# Esquematico.net
KiCad netlist of a schematic drawn in Altium Designer
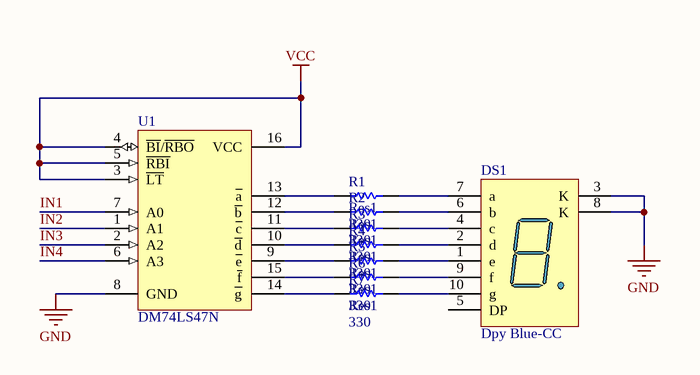
[diagram p0: Esquematico.SchDoc]

(export (version "E")
  (design (tool "Eeschema 10.0.6"))
  (components
    (comp (ref "DS1")
      (value "Dpy Blue-CC")
      (footprint "H")
      (description "14.2 mm General Purpose Blue 7-Segment Display: CC, RH DP, Gray Surface")
      (fields (field (name "PUBLISHER") "Altium Limited"))
      (libsource (lib "Miscellaneous Devices") (part "Dpy Blue-CC"))
    )
    (comp (ref "R1")
      (value "Res1")
      (footprint "AXIAL-0.3")
      (description "Resistor")
      (fields (field (name "ALTIUM_VALUE") "330") (field (name "PUBLISHER") "Altium Limited"))
      (libsource (lib "Miscellaneous Devices") (part "Res1"))
    )
    (comp (ref "R2")
      (value "Res1")
      (footprint "AXIAL-0.3")
      (description "Resistor")
      (fields (field (name "ALTIUM_VALUE") "330") (field (name "PUBLISHER") "Altium Limited"))
      (libsource (lib "Miscellaneous Devices") (part "Res1"))
    )
    (comp (ref "R3")
      (value "Res1")
      (footprint "AXIAL-0.3")
      (description "Resistor")
      (fields (field (name "ALTIUM_VALUE") "330") (field (name "PUBLISHER") "Altium Limited"))
      (libsource (lib "Miscellaneous Devices") (part "Res1"))
    )
    (comp (ref "R4")
      (value "Res1")
      (footprint "AXIAL-0.3")
      (description "Resistor")
      (fields (field (name "ALTIUM_VALUE") "330") (field (name "PUBLISHER") "Altium Limited"))
      (libsource (lib "Miscellaneous Devices") (part "Res1"))
    )
    (comp (ref "R5")
      (value "Res1")
      (footprint "AXIAL-0.3")
      (description "Resistor")
      (fields (field (name "ALTIUM_VALUE") "330") (field (name "PUBLISHER") "Altium Limited"))
      (libsource (lib "Miscellaneous Devices") (part "Res1"))
    )
    (comp (ref "R6")
      (value "Res1")
      (footprint "AXIAL-0.3")
      (description "Resistor")
      (fields (field (name "ALTIUM_VALUE") "330") (field (name "PUBLISHER") "Altium Limited"))
      (libsource (lib "Miscellaneous Devices") (part "Res1"))
    )
    (comp (ref "R7")
      (value "Res1")
      (footprint "AXIAL-0.3")
      (description "Resistor")
      (fields (field (name "ALTIUM_VALUE") "330") (field (name "PUBLISHER") "Altium Limited"))
      (libsource (lib "Miscellaneous Devices") (part "Res1"))
    )
    (comp (ref "U1")
      (value "DM74LS47N")
      (footprint "N16E")
      (description "BCD to 7-Segment Decoder/Driver with Open-Collector Output")
      (fields (field (name "PUBLISHER") "Altium Limited"))
      (libsource (lib "FSC Interface Display Driver") (part "DM74LS47N"))
    )
  )
  (nets
    (net (code "1") (name "/IN1") (class "Default")
      (node (ref "U1") (pin "7") (pinfunction "A0_7") (pintype "input"))
    )
    (net (code "2") (name "/IN2") (class "Default")
      (node (ref "U1") (pin "1") (pinfunction "A1_1") (pintype "input"))
    )
    (net (code "3") (name "/IN3") (class "Default")
      (node (ref "U1") (pin "2") (pinfunction "A2_2") (pintype "input"))
    )
    (net (code "4") (name "/IN4") (class "Default")
      (node (ref "U1") (pin "6") (pinfunction "A3_6") (pintype "input"))
    )
    (net (code "5") (name "GND") (class "Default")
      (node (ref "DS1") (pin "3") (pinfunction "K_3") (pintype "passive"))
      (node (ref "DS1") (pin "8") (pinfunction "K_8") (pintype "passive"))
      (node (ref "U1") (pin "8") (pinfunction "GND_8") (pintype "power_in"))
    )
    (net (code "6") (name "Net-(DS1-a)") (class "Default")
      (node (ref "DS1") (pin "7") (pinfunction "a_7") (pintype "passive"))
      (node (ref "R1") (pin "2") (pinfunction "2_2") (pintype "passive"))
    )
    (net (code "7") (name "Net-(DS1-b)") (class "Default")
      (node (ref "DS1") (pin "6") (pinfunction "b_6") (pintype "passive"))
      (node (ref "R2") (pin "2") (pinfunction "2_2") (pintype "passive"))
    )
    (net (code "8") (name "Net-(DS1-c)") (class "Default")
      (node (ref "DS1") (pin "4") (pinfunction "c_4") (pintype "passive"))
      (node (ref "R3") (pin "2") (pinfunction "2_2") (pintype "passive"))
    )
    (net (code "9") (name "Net-(DS1-d)") (class "Default")
      (node (ref "DS1") (pin "2") (pinfunction "d_2") (pintype "passive"))
      (node (ref "R4") (pin "2") (pinfunction "2_2") (pintype "passive"))
    )
    (net (code "10") (name "Net-(DS1-e)") (class "Default")
      (node (ref "DS1") (pin "1") (pinfunction "e_1") (pintype "passive"))
      (node (ref "R5") (pin "2") (pinfunction "2_2") (pintype "passive"))
    )
    (net (code "11") (name "Net-(DS1-f)") (class "Default")
      (node (ref "DS1") (pin "9") (pinfunction "f_9") (pintype "passive"))
      (node (ref "R6") (pin "2") (pinfunction "2_2") (pintype "passive"))
    )
    (net (code "12") (name "Net-(DS1-g)") (class "Default")
      (node (ref "DS1") (pin "10") (pinfunction "g_10") (pintype "passive"))
      (node (ref "R7") (pin "2") (pinfunction "2_2") (pintype "passive"))
    )
    (net (code "13") (name "Net-(U1-~{a})") (class "Default")
      (node (ref "R1") (pin "1") (pinfunction "1_1") (pintype "passive"))
      (node (ref "U1") (pin "13") (pinfunction "~{a}_13") (pintype "open_collector"))
    )
    (net (code "14") (name "Net-(U1-~{b})") (class "Default")
      (node (ref "R2") (pin "1") (pinfunction "1_1") (pintype "passive"))
      (node (ref "U1") (pin "12") (pinfunction "~{b}_12") (pintype "open_collector"))
    )
    (net (code "15") (name "Net-(U1-~{c})") (class "Default")
      (node (ref "R3") (pin "1") (pinfunction "1_1") (pintype "passive"))
      (node (ref "U1") (pin "11") (pinfunction "~{c}_11") (pintype "open_collector"))
    )
    (net (code "16") (name "Net-(U1-~{d})") (class "Default")
      (node (ref "R4") (pin "1") (pinfunction "1_1") (pintype "passive"))
      (node (ref "U1") (pin "10") (pinfunction "~{d}_10") (pintype "open_collector"))
    )
    (net (code "17") (name "Net-(U1-~{e})") (class "Default")
      (node (ref "R5") (pin "1") (pinfunction "1_1") (pintype "passive"))
      (node (ref "U1") (pin "9") (pinfunction "~{e}_9") (pintype "open_collector"))
    )
    (net (code "18") (name "Net-(U1-~{f})") (class "Default")
      (node (ref "R6") (pin "1") (pinfunction "1_1") (pintype "passive"))
      (node (ref "U1") (pin "15") (pinfunction "~{f}_15") (pintype "open_collector"))
    )
    (net (code "19") (name "Net-(U1-~{g})") (class "Default")
      (node (ref "R7") (pin "1") (pinfunction "1_1") (pintype "passive"))
      (node (ref "U1") (pin "14") (pinfunction "~{g}_14") (pintype "open_collector"))
    )
    (net (code "20") (name "VCC") (class "Default")
      (node (ref "U1") (pin "16") (pinfunction "VCC_16") (pintype "power_in"))
      (node (ref "U1") (pin "3") (pinfunction "~{LT}_3") (pintype "input"))
      (node (ref "U1") (pin "4") (pinfunction "~{BI}/~{RBO}_4") (pintype "bidirectional"))
      (node (ref "U1") (pin "5") (pinfunction "~{RBI}_5") (pintype "input"))
    )
    (net (code "21") (name "unconnected-(DS1-DP-Pad5)") (class "Default")
      (node (ref "DS1") (pin "5") (pinfunction "DP_5") (pintype "passive"))
    )
  )
)
